# trinamic-controller.net
KiCad netlist of a schematic drawn in Altium Designer
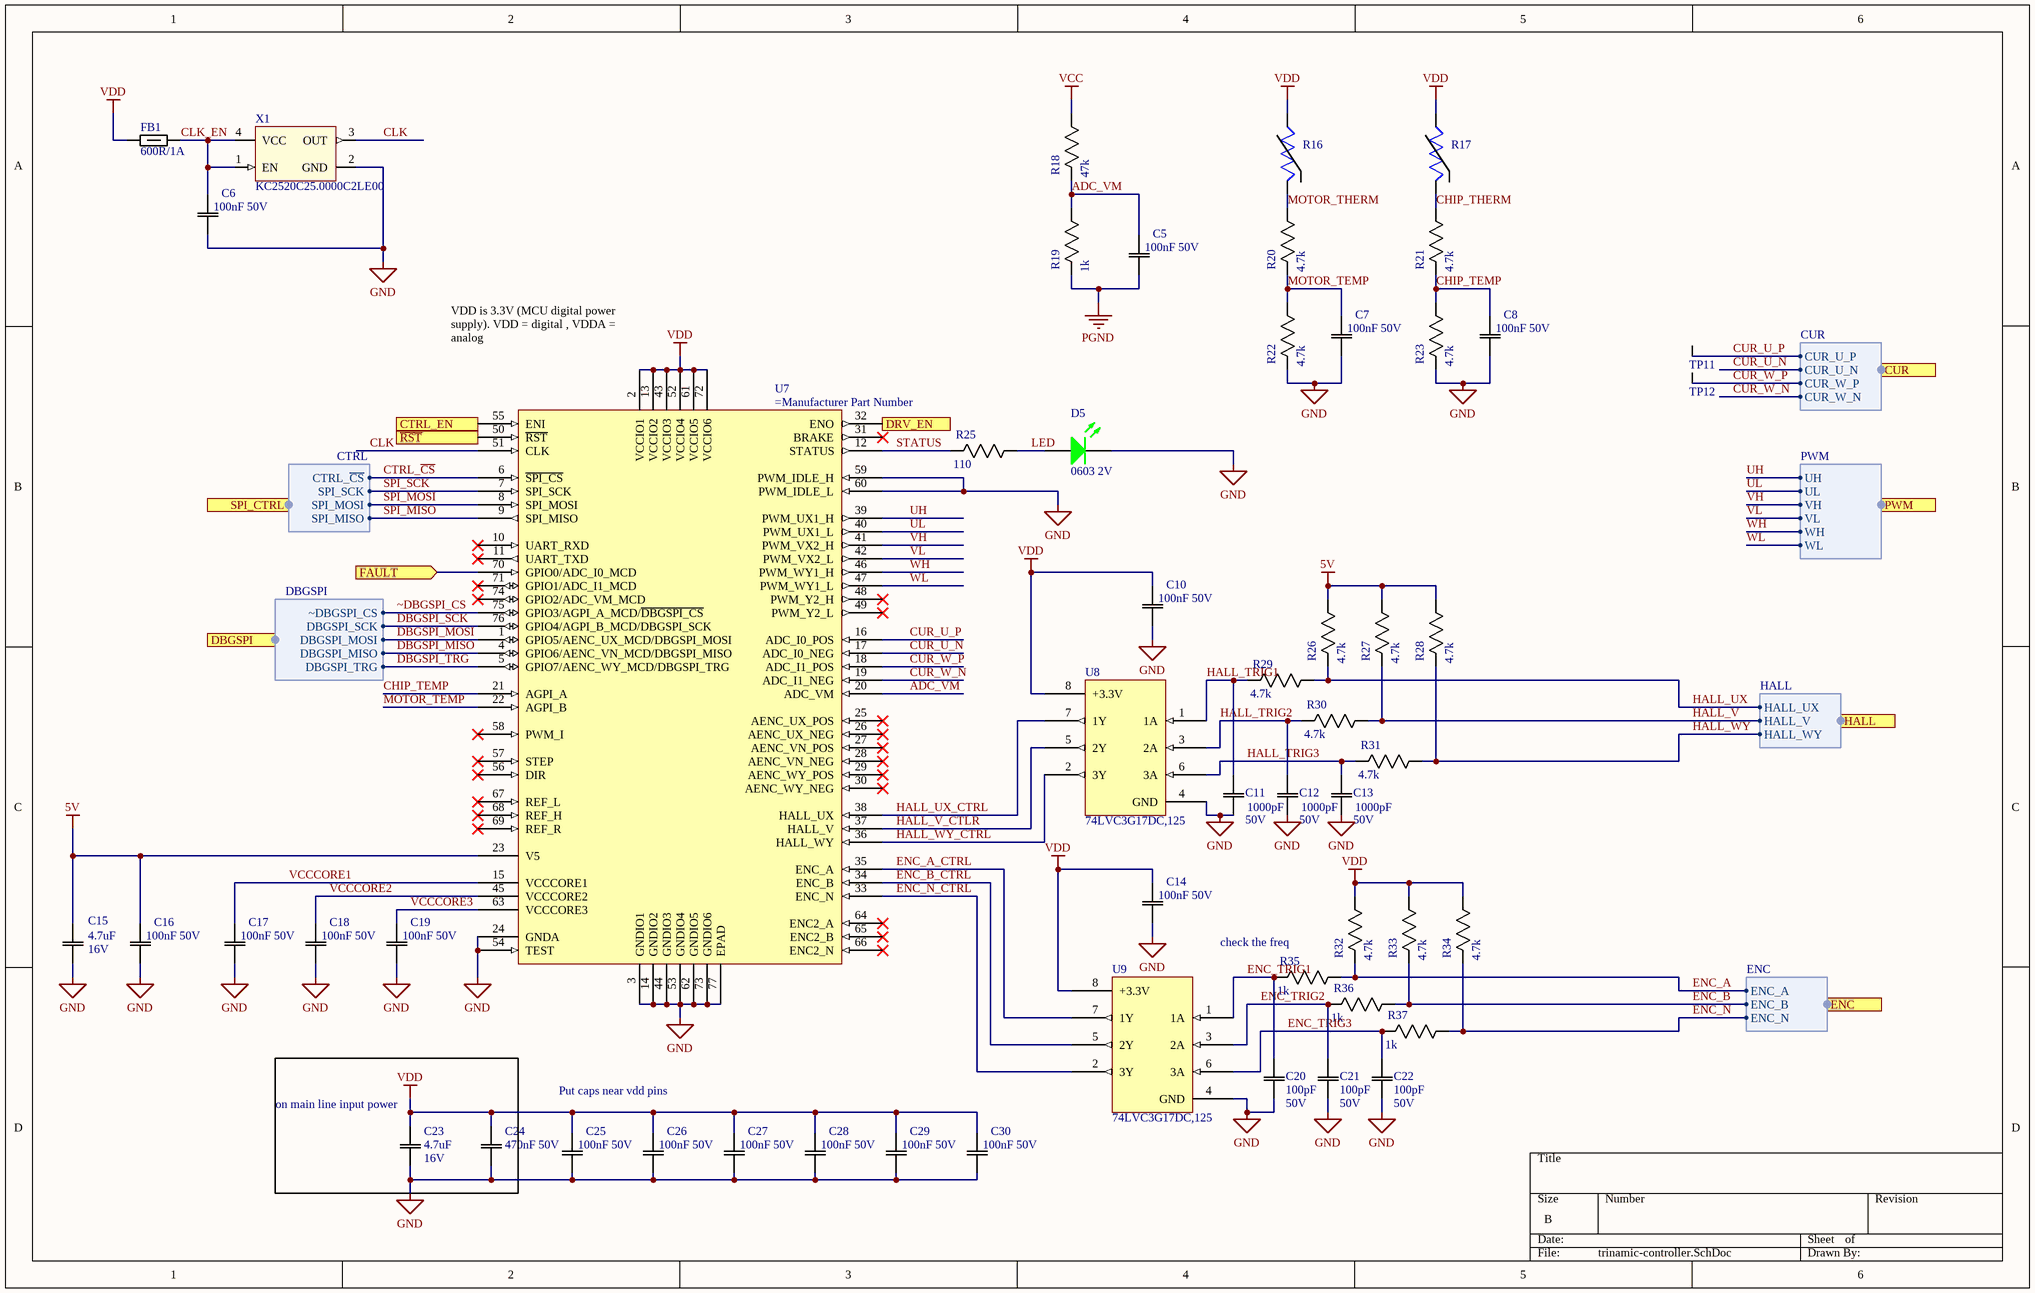
[diagram p0: trinamic-controller.SchDoc]

(export (version "E")
  (design (tool "Eeschema 10.0.6"))
  (components
    (comp (ref "C5")
      (value "100nF 50V")
      (footprint "0603")
      (description "Default Symbol for Capacitors")
      (fields (field (name "TOLERANCE") "10%") (field (name "PART NUMBER") "CAP 100nF 50V"))
      (libsource (lib "capacitor_library") (part "CAP_Default"))
    )
    (comp (ref "C6")
      (value "100nF 50V")
      (footprint "0603")
      (description "Default Symbol for Capacitors")
      (fields (field (name "TOLERANCE") "10%") (field (name "PART NUMBER") "CAP 100nF 50V"))
      (libsource (lib "capacitor_library") (part "CAP_Default"))
    )
    (comp (ref "C7")
      (value "100nF 50V")
      (footprint "0603")
      (description "Default Symbol for Capacitors")
      (fields (field (name "TOLERANCE") "10%") (field (name "PART NUMBER") "CAP 100nF 50V"))
      (libsource (lib "capacitor_library") (part "CAP_Default"))
    )
    (comp (ref "C8")
      (value "100nF 50V")
      (footprint "0603")
      (description "Default Symbol for Capacitors")
      (fields (field (name "TOLERANCE") "10%") (field (name "PART NUMBER") "CAP 100nF 50V"))
      (libsource (lib "capacitor_library") (part "CAP_Default"))
    )
    (comp (ref "C10")
      (value "100nF 50V")
      (footprint "0603")
      (description "Default Symbol for Capacitors")
      (fields (field (name "TOLERANCE") "10%") (field (name "PART NUMBER") "CAP 100nF 50V"))
      (libsource (lib "capacitor_library") (part "CAP_Default"))
    )
    (comp (ref "C11")
      (value "1000pF")
      (footprint "0603")
      (description "Default Symbol for Capacitors")
      (fields
        (field (name "TOLERANCE") "10%")
        (field (name "RATING") "50V")
        (field (name "PART NUMBER") "CAP 1000pF 50V")
      )
      (libsource (lib "capacitor_library") (part "CAP_Default"))
    )
    (comp (ref "C12")
      (value "1000pF")
      (footprint "0603")
      (description "Default Symbol for Capacitors")
      (fields
        (field (name "TOLERANCE") "10%")
        (field (name "RATING") "50V")
        (field (name "PART NUMBER") "CAP 1000pF 50V")
      )
      (libsource (lib "capacitor_library") (part "CAP_Default"))
    )
    (comp (ref "C13")
      (value "1000pF")
      (footprint "0603")
      (description "Default Symbol for Capacitors")
      (fields
        (field (name "TOLERANCE") "10%")
        (field (name "RATING") "50V")
        (field (name "PART NUMBER") "CAP 1000pF 50V")
      )
      (libsource (lib "capacitor_library") (part "CAP_Default"))
    )
    (comp (ref "C14")
      (value "100nF 50V")
      (footprint "0603")
      (description "Default Symbol for Capacitors")
      (fields (field (name "TOLERANCE") "10%") (field (name "PART NUMBER") "CAP 100nF 50V"))
      (libsource (lib "capacitor_library") (part "CAP_Default"))
    )
    (comp (ref "C15")
      (value "4.7uF")
      (footprint "0603")
      (description "Default Symbol for Capacitors")
      (fields
        (field (name "TOLERANCE") "10%")
        (field (name "RATING") "16V")
        (field (name "PART NUMBER") "CAP 4.7uF 16V")
      )
      (libsource (lib "capacitor_library") (part "CAP_Default"))
    )
    (comp (ref "C16")
      (value "100nF 50V")
      (footprint "0603")
      (description "Default Symbol for Capacitors")
      (fields (field (name "TOLERANCE") "10%") (field (name "PART NUMBER") "CAP 100nF 50V"))
      (libsource (lib "capacitor_library") (part "CAP_Default"))
    )
    (comp (ref "C17")
      (value "100nF 50V")
      (footprint "0603")
      (description "Default Symbol for Capacitors")
      (fields (field (name "TOLERANCE") "10%") (field (name "PART NUMBER") "CAP 100nF 50V"))
      (libsource (lib "capacitor_library") (part "CAP_Default"))
    )
    (comp (ref "C18")
      (value "100nF 50V")
      (footprint "0603")
      (description "Default Symbol for Capacitors")
      (fields (field (name "TOLERANCE") "10%") (field (name "PART NUMBER") "CAP 100nF 50V"))
      (libsource (lib "capacitor_library") (part "CAP_Default"))
    )
    (comp (ref "C19")
      (value "100nF 50V")
      (footprint "0603")
      (description "Default Symbol for Capacitors")
      (fields (field (name "TOLERANCE") "10%") (field (name "PART NUMBER") "CAP 100nF 50V"))
      (libsource (lib "capacitor_library") (part "CAP_Default"))
    )
    (comp (ref "C20")
      (value "100pF")
      (footprint "0603")
      (description "Default Symbol for Capacitors")
      (fields
        (field (name "TOLERANCE") "10%")
        (field (name "RATING") "50V")
        (field (name "PART NUMBER") "CAP 100pF 50V")
      )
      (libsource (lib "capacitor_library") (part "CAP_Default"))
    )
    (comp (ref "C21")
      (value "100pF")
      (footprint "0603")
      (description "Default Symbol for Capacitors")
      (fields
        (field (name "TOLERANCE") "10%")
        (field (name "RATING") "50V")
        (field (name "PART NUMBER") "CAP 100pF 50V")
      )
      (libsource (lib "capacitor_library") (part "CAP_Default"))
    )
    (comp (ref "C22")
      (value "100pF")
      (footprint "0603")
      (description "Default Symbol for Capacitors")
      (fields
        (field (name "TOLERANCE") "10%")
        (field (name "RATING") "50V")
        (field (name "PART NUMBER") "CAP 100pF 50V")
      )
      (libsource (lib "capacitor_library") (part "CAP_Default"))
    )
    (comp (ref "C23")
      (value "4.7uF")
      (footprint "0603")
      (description "Default Symbol for Capacitors")
      (fields
        (field (name "TOLERANCE") "10%")
        (field (name "RATING") "16V")
        (field (name "PART NUMBER") "CAP 4.7uF 16V")
      )
      (libsource (lib "capacitor_library") (part "CAP_Default"))
    )
    (comp (ref "C24")
      (value "470nF 50V")
      (footprint "0603")
      (description "Default Symbol for Capacitors")
      (fields (field (name "TOLERANCE") "10%") (field (name "PART NUMBER") "CAP 470nF 50V"))
      (libsource (lib "capacitor_library") (part "CAP_Default"))
    )
    (comp (ref "C25")
      (value "100nF 50V")
      (footprint "0603")
      (description "Default Symbol for Capacitors")
      (fields (field (name "TOLERANCE") "10%") (field (name "PART NUMBER") "CAP 100nF 50V"))
      (libsource (lib "capacitor_library") (part "CAP_Default"))
    )
    (comp (ref "C26")
      (value "100nF 50V")
      (footprint "0603")
      (description "Default Symbol for Capacitors")
      (fields (field (name "TOLERANCE") "10%") (field (name "PART NUMBER") "CAP 100nF 50V"))
      (libsource (lib "capacitor_library") (part "CAP_Default"))
    )
    (comp (ref "C27")
      (value "100nF 50V")
      (footprint "0603")
      (description "Default Symbol for Capacitors")
      (fields (field (name "TOLERANCE") "10%") (field (name "PART NUMBER") "CAP 100nF 50V"))
      (libsource (lib "capacitor_library") (part "CAP_Default"))
    )
    (comp (ref "C28")
      (value "100nF 50V")
      (footprint "0603")
      (description "Default Symbol for Capacitors")
      (fields (field (name "TOLERANCE") "10%") (field (name "PART NUMBER") "CAP 100nF 50V"))
      (libsource (lib "capacitor_library") (part "CAP_Default"))
    )
    (comp (ref "C29")
      (value "100nF 50V")
      (footprint "0603")
      (description "Default Symbol for Capacitors")
      (fields (field (name "TOLERANCE") "10%") (field (name "PART NUMBER") "CAP 100nF 50V"))
      (libsource (lib "capacitor_library") (part "CAP_Default"))
    )
    (comp (ref "C30")
      (value "100nF 50V")
      (footprint "0603")
      (description "Default Symbol for Capacitors")
      (fields (field (name "TOLERANCE") "10%") (field (name "PART NUMBER") "CAP 100nF 50V"))
      (libsource (lib "capacitor_library") (part "CAP_Default"))
    )
    (comp (ref "D5")
      (value "0603 2V")
      (footprint "0603 - LED")
      (description "LED Uni-Color Green 574nm 2-Pin Chip LED T/R")
      (fields (field (name "PART NUMBER") "LED GREEN SMD 0603"))
      (libsource (lib "Diode_Library") (part "LED GREEN SMD 0603"))
    )
    (comp (ref "FB1")
      (value "600R/1A")
      (footprint "0603")
      (fields (field (name "PART NUMBER") "FERRITE BEAD 200 MOHM 0603 1LN"))
      (libsource (lib "Inductor_Library") (part "FERRITE BEAD 200 MOHM 0603 1LN"))
    )
    (comp (ref "R16")
      (value "RES NTC 10k")
      (footprint "THERMISTOR TH")
      (fields (field (name "PART NUMBER") "RES NTC 10k TH") (field (name "TOLERANCE") "1%"))
      (libsource (lib "Resistor_Library") (part "RES NTC 10k"))
    )
    (comp (ref "R17")
      (value "RES NTC 10k")
      (footprint "0603")
      (fields (field (name "PART NUMBER") "RES NTC 10k CHIP") (field (name "TOLERANCE") "1%"))
      (libsource (lib "Resistor_Library") (part "RES NTC 10k"))
    )
    (comp (ref "R18")
      (value "47k")
      (footprint "0603")
      (description "Default Resistor Symbol")
      (fields (field (name "TOLERANCE") "1%") (field (name "PART NUMBER") "RES 47k 1/8W - 1%"))
      (libsource (lib "") (part "RES_DEFAULT_1"))
    )
    (comp (ref "R19")
      (value "1k")
      (footprint "0603")
      (description "Default Resistor Symbol")
      (fields (field (name "TOLERANCE") "1%") (field (name "PART NUMBER") "RES 1k 1/8W - 1%"))
      (libsource (lib "Resistor_Library") (part "RES_DEFAULT"))
    )
    (comp (ref "R20")
      (value "4.7k")
      (footprint "0603")
      (description "Default Resistor Symbol")
      (fields (field (name "TOLERANCE") "1%") (field (name "PART NUMBER") "RES 4.7k 1/8W - 1%"))
      (libsource (lib "") (part "RES_DEFAULT_1"))
    )
    (comp (ref "R21")
      (value "4.7k")
      (footprint "0603")
      (description "Default Resistor Symbol")
      (fields (field (name "TOLERANCE") "1%") (field (name "PART NUMBER") "RES 4.7k 1/8W - 1%"))
      (libsource (lib "") (part "RES_DEFAULT_1"))
    )
    (comp (ref "R22")
      (value "4.7k")
      (footprint "0603")
      (description "Default Resistor Symbol")
      (fields (field (name "TOLERANCE") "1%") (field (name "PART NUMBER") "RES 4.7k 1/8W - 1%"))
      (libsource (lib "") (part "RES_DEFAULT_1"))
    )
    (comp (ref "R23")
      (value "4.7k")
      (footprint "0603")
      (description "Default Resistor Symbol")
      (fields (field (name "TOLERANCE") "1%") (field (name "PART NUMBER") "RES 4.7k 1/8W - 1%"))
      (libsource (lib "") (part "RES_DEFAULT_1"))
    )
    (comp (ref "R25")
      (value "110")
      (footprint "0603")
      (description "Default Resistor Symbol")
      (fields (field (name "TOLERANCE") "1%") (field (name "PART NUMBER") "RES 110.0 1/8W - 1%"))
      (libsource (lib "Resistor_Library") (part "RES_DEFAULT"))
    )
    (comp (ref "R26")
      (value "4.7k")
      (footprint "0603")
      (description "Default Resistor Symbol")
      (fields (field (name "TOLERANCE") "5%") (field (name "PART NUMBER") "RES 4.7k 1/8W - 5%"))
      (libsource (lib "Resistor_Library") (part "RES_DEFAULT"))
    )
    (comp (ref "R27")
      (value "4.7k")
      (footprint "0603")
      (description "Default Resistor Symbol")
      (fields (field (name "TOLERANCE") "5%") (field (name "PART NUMBER") "RES 4.7k 1/8W - 5%"))
      (libsource (lib "Resistor_Library") (part "RES_DEFAULT"))
    )
    (comp (ref "R28")
      (value "4.7k")
      (footprint "0603")
      (description "Default Resistor Symbol")
      (fields (field (name "TOLERANCE") "5%") (field (name "PART NUMBER") "RES 4.7k 1/8W - 5%"))
      (libsource (lib "") (part "RES_DEFAULT_1"))
    )
    (comp (ref "R29")
      (value "4.7k")
      (footprint "0603")
      (description "Default Resistor Symbol")
      (fields (field (name "TOLERANCE") "5%") (field (name "PART NUMBER") "RES 4.7k 1/8W - 5%"))
      (libsource (lib "Resistor_Library") (part "RES_DEFAULT"))
    )
    (comp (ref "R30")
      (value "4.7k")
      (footprint "0603")
      (description "Default Resistor Symbol")
      (fields (field (name "TOLERANCE") "5%") (field (name "PART NUMBER") "RES 4.7k 1/8W - 5%"))
      (libsource (lib "Resistor_Library") (part "RES_DEFAULT"))
    )
    (comp (ref "R31")
      (value "4.7k")
      (footprint "0603")
      (description "Default Resistor Symbol")
      (fields (field (name "TOLERANCE") "5%") (field (name "PART NUMBER") "RES 4.7k 1/8W - 5%"))
      (libsource (lib "Resistor_Library") (part "RES_DEFAULT"))
    )
    (comp (ref "R32")
      (value "4.7k")
      (footprint "0603")
      (description "Default Resistor Symbol")
      (fields (field (name "TOLERANCE") "5%") (field (name "PART NUMBER") "RES 4.7k 1/8W - 5%"))
      (libsource (lib "Resistor_Library") (part "RES_DEFAULT"))
    )
    (comp (ref "R33")
      (value "4.7k")
      (footprint "0603")
      (description "Default Resistor Symbol")
      (fields (field (name "TOLERANCE") "5%") (field (name "PART NUMBER") "RES 4.7k 1/8W - 5%"))
      (libsource (lib "Resistor_Library") (part "RES_DEFAULT"))
    )
    (comp (ref "R34")
      (value "4.7k")
      (footprint "0603")
      (description "Default Resistor Symbol")
      (fields (field (name "TOLERANCE") "5%") (field (name "PART NUMBER") "RES 4.7k 1/8W - 5%"))
      (libsource (lib "") (part "RES_DEFAULT_1"))
    )
    (comp (ref "R35")
      (value "1k")
      (footprint "0603")
      (description "Default Resistor Symbol")
      (fields (field (name "TOLERANCE") "1%") (field (name "PART NUMBER") "RES 1k 1/8W - 1%"))
      (libsource (lib "") (part "RES_DEFAULT_1"))
    )
    (comp (ref "R36")
      (value "1k")
      (footprint "0603")
      (description "Default Resistor Symbol")
      (fields (field (name "TOLERANCE") "1%") (field (name "PART NUMBER") "RES 1k 1/8W - 1%"))
      (libsource (lib "Resistor_Library") (part "RES_DEFAULT"))
    )
    (comp (ref "R37")
      (value "1k")
      (footprint "0603")
      (description "Default Resistor Symbol")
      (fields (field (name "TOLERANCE") "1%") (field (name "PART NUMBER") "RES 1k 1/8W - 1%"))
      (libsource (lib "") (part "RES_DEFAULT_1"))
    )
    (comp (ref "TP11")
      (value "Test Point (Via)")
      (footprint "TP")
      (libsource (lib "IC_Library") (part "Test Point (Via)"))
    )
    (comp (ref "TP12")
      (value "Test Point (Via)")
      (footprint "TP")
      (libsource (lib "IC_Library") (part "Test Point (Via)"))
    )
    (comp (ref "U7")
      (value "~")
      (footprint "QFN40P1050X650X90_HS-77N")
      (description "Motor Driver, -40 To 125Deg C Rohs Compliant: Yes")
      (fields (field (name "PART NUMBER") "TMC4671"))
      (libsource (lib "IC_Library") (part "TMC4671"))
    )
    (comp (ref "U8")
      (value "74LVC3G17DC,125")
      (footprint "8-VSSOP")
      (description "IC BUFFER TRIPLE SCHMITT TRIGGER 5.5V VSSOP-8")
      (fields (field (name "PART NUMBER") "IC 74LVC3G17DC,125"))
      (libsource (lib "IC_Library") (part "IC 74LVC3G17DC,125"))
    )
    (comp (ref "U9")
      (value "74LVC3G17DC,125")
      (footprint "8-VSSOP")
      (description "IC BUFFER TRIPLE SCHMITT TRIGGER 5.5V VSSOP-8")
      (fields (field (name "PART NUMBER") "IC 74LVC3G17DC,125"))
      (libsource (lib "IC_Library") (part "IC 74LVC3G17DC,125"))
    )
    (comp (ref "X1")
      (value "KC2520C25.0000C2LE00")
      (footprint "KC2520C25.0000C2LE00")
      (description "Oscillator XO 25MHz ±15ppm 15pF CMOS 55% 2.5V/3.3V 4-Pin Mini-CSMD T/R")
      (fields (field (name "PART NUMBER") "XTAL OSC 25MHz 3.3V"))
      (libsource (lib "Oscillator_Library") (part "XTAL OSC 25MHz 3.3V"))
    )
  )
  (nets
    (net (code "7") (name "/ADC_VM") (class "Default")
      (node (ref "C5") (pin "2") (pinfunction "C2_2") (pintype "passive"))
      (node (ref "R18") (pin "2") (pinfunction "R2_2") (pintype "passive"))
      (node (ref "R19") (pin "1") (pinfunction "R1_1") (pintype "passive"))
      (node (ref "U7") (pin "20") (pinfunction "ADC_VM_20") (pintype "input"))
    )
    (net (code "8") (name "/CHIP_TEMP") (class "Default")
      (node (ref "C8") (pin "2") (pinfunction "C2_2") (pintype "passive"))
      (node (ref "R21") (pin "2") (pinfunction "R2_2") (pintype "passive"))
      (node (ref "R23") (pin "1") (pinfunction "R1_1") (pintype "passive"))
      (node (ref "U7") (pin "21") (pinfunction "AGPI_A_21") (pintype "input"))
    )
    (net (code "9") (name "/CHIP_THERM") (class "Default")
      (node (ref "R17") (pin "1") (pinfunction "1_1") (pintype "passive"))
      (node (ref "R21") (pin "1") (pinfunction "R1_1") (pintype "passive"))
    )
    (net (code "10") (name "/CLK") (class "Default")
      (node (ref "U7") (pin "51") (pinfunction "CLK_51") (pintype "input"))
      (node (ref "X1") (pin "3") (pinfunction "OUT_3") (pintype "output"))
    )
    (net (code "11") (name "/CLK_EN") (class "Default")
      (node (ref "C6") (pin "2") (pinfunction "C2_2") (pintype "passive"))
      (node (ref "FB1") (pin "2") (pinfunction "2_2") (pintype "passive"))
      (node (ref "X1") (pin "1") (pinfunction "EN_1") (pintype "input"))
      (node (ref "X1") (pin "4") (pinfunction "VCC_4") (pintype "power_in"))
    )
    (net (code "12") (name "/CTRL_EN") (class "Default")
      (node (ref "U7") (pin "55") (pinfunction "ENI_55") (pintype "input"))
    )
    (net (code "13") (name "/CTRL_~{CS}") (class "Default")
      (node (ref "U7") (pin "6") (pinfunction "~{SPI_CS}_6") (pintype "input"))
    )
    (net (code "14") (name "/CUR_U_N") (class "Default")
      (node (ref "U7") (pin "17") (pinfunction "ADC_I0_NEG_17") (pintype "input"))
    )
    (net (code "15") (name "/CUR_U_P") (class "Default")
      (node (ref "TP11") (pin "1") (pinfunction "1_1") (pintype "passive"))
      (node (ref "U7") (pin "16") (pinfunction "ADC_I0_POS_16") (pintype "input"))
    )
    (net (code "16") (name "/CUR_W_N") (class "Default")
      (node (ref "U7") (pin "19") (pinfunction "ADC_I1_NEG_19") (pintype "input"))
    )
    (net (code "17") (name "/CUR_W_P") (class "Default")
      (node (ref "TP12") (pin "1") (pinfunction "1_1") (pintype "passive"))
      (node (ref "U7") (pin "18") (pinfunction "ADC_I1_POS_18") (pintype "input"))
    )
    (net (code "18") (name "/DBGSPI_MISO") (class "Default")
      (node (ref "U7") (pin "4") (pinfunction "GPIO6/AENC_VN_MCD/DBGSPI_MISO_4") (pintype "bidirectional"))
    )
    (net (code "19") (name "/DBGSPI_MOSI") (class "Default")
      (node (ref "U7") (pin "1") (pinfunction "GPIO5/AENC_UX_MCD/DBGSPI_MOSI_1") (pintype "bidirectional"))
    )
    (net (code "20") (name "/DBGSPI_SCK") (class "Default")
      (node (ref "U7") (pin "76") (pinfunction "GPIO4/AGPI_B_MCD/DBGSPI_SCK_76") (pintype "bidirectional"))
    )
    (net (code "21") (name "/DBGSPI_TRG") (class "Default")
      (node (ref "U7") (pin "5") (pinfunction "GPIO7/AENC_WY_MCD/DBGSPI_TRG_5") (pintype "bidirectional"))
    )
    (net (code "22") (name "/DRV_EN") (class "Default")
      (node (ref "U7") (pin "32") (pinfunction "ENO_32") (pintype "output"))
    )
    (net (code "23") (name "/ENC_A") (class "Default")
      (node (ref "R32") (pin "2") (pinfunction "R2_2") (pintype "passive"))
      (node (ref "R35") (pin "1") (pinfunction "R1_1") (pintype "passive"))
    )
    (net (code "24") (name "/ENC_A_CTRL") (class "Default")
      (node (ref "U7") (pin "35") (pinfunction "ENC_A_35") (pintype "input"))
      (node (ref "U9") (pin "7") (pinfunction "1Y_7") (pintype "output"))
    )
    (net (code "25") (name "/ENC_B") (class "Default")
      (node (ref "R33") (pin "2") (pinfunction "R2_2") (pintype "passive"))
      (node (ref "R36") (pin "1") (pinfunction "R1_1") (pintype "passive"))
    )
    (net (code "26") (name "/ENC_B_CTRL") (class "Default")
      (node (ref "U7") (pin "34") (pinfunction "ENC_B_34") (pintype "input"))
      (node (ref "U9") (pin "5") (pinfunction "2Y_5") (pintype "output"))
    )
    (net (code "27") (name "/ENC_N") (class "Default")
      (node (ref "R34") (pin "2") (pinfunction "R2_2") (pintype "passive"))
      (node (ref "R37") (pin "1") (pinfunction "R1_1") (pintype "passive"))
    )
    (net (code "28") (name "/ENC_N_CTRL") (class "Default")
      (node (ref "U7") (pin "33") (pinfunction "ENC_N_33") (pintype "input"))
      (node (ref "U9") (pin "2") (pinfunction "3Y_2") (pintype "output"))
    )
    (net (code "29") (name "/ENC_TRIG1") (class "Default")
      (node (ref "C20") (pin "2") (pinfunction "C2_2") (pintype "passive"))
      (node (ref "R35") (pin "2") (pinfunction "R2_2") (pintype "passive"))
      (node (ref "U9") (pin "1") (pinfunction "1A_1") (pintype "input"))
    )
    (net (code "30") (name "/ENC_TRIG2") (class "Default")
      (node (ref "C21") (pin "2") (pinfunction "C2_2") (pintype "passive"))
      (node (ref "R36") (pin "2") (pinfunction "R2_2") (pintype "passive"))
      (node (ref "U9") (pin "3") (pinfunction "2A_3") (pintype "input"))
    )
    (net (code "31") (name "/ENC_TRIG3") (class "Default")
      (node (ref "C22") (pin "2") (pinfunction "C2_2") (pintype "passive"))
      (node (ref "R37") (pin "2") (pinfunction "R2_2") (pintype "passive"))
      (node (ref "U9") (pin "6") (pinfunction "3A_6") (pintype "input"))
    )
    (net (code "32") (name "/FAULT") (class "Default")
      (node (ref "U7") (pin "70") (pinfunction "GPIO0/ADC_I0_MCD_70") (pintype "input"))
    )
    (net (code "33") (name "/HALL_TRIG1") (class "Default")
      (node (ref "C11") (pin "2") (pinfunction "C2_2") (pintype "passive"))
      (node (ref "R29") (pin "2") (pinfunction "R2_2") (pintype "passive"))
      (node (ref "U8") (pin "1") (pinfunction "1A_1") (pintype "input"))
    )
    (net (code "34") (name "/HALL_TRIG2") (class "Default")
      (node (ref "C12") (pin "2") (pinfunction "C2_2") (pintype "passive"))
      (node (ref "R30") (pin "2") (pinfunction "R2_2") (pintype "passive"))
      (node (ref "U8") (pin "3") (pinfunction "2A_3") (pintype "input"))
    )
    (net (code "35") (name "/HALL_TRIG3") (class "Default")
      (node (ref "C13") (pin "2") (pinfunction "C2_2") (pintype "passive"))
      (node (ref "R31") (pin "2") (pinfunction "R2_2") (pintype "passive"))
      (node (ref "U8") (pin "6") (pinfunction "3A_6") (pintype "input"))
    )
    (net (code "36") (name "/HALL_UX") (class "Default")
      (node (ref "R26") (pin "2") (pinfunction "R2_2") (pintype "passive"))
      (node (ref "R29") (pin "1") (pinfunction "R1_1") (pintype "passive"))
    )
    (net (code "37") (name "/HALL_UX_CTRL") (class "Default")
      (node (ref "U7") (pin "38") (pinfunction "HALL_UX_38") (pintype "input"))
      (node (ref "U8") (pin "7") (pinfunction "1Y_7") (pintype "output"))
    )
    (net (code "38") (name "/HALL_V") (class "Default")
      (node (ref "R27") (pin "2") (pinfunction "R2_2") (pintype "passive"))
      (node (ref "R30") (pin "1") (pinfunction "R1_1") (pintype "passive"))
    )
    (net (code "39") (name "/HALL_V_CTLR") (class "Default")
      (node (ref "U7") (pin "37") (pinfunction "HALL_V_37") (pintype "input"))
      (node (ref "U8") (pin "5") (pinfunction "2Y_5") (pintype "output"))
    )
    (net (code "40") (name "/HALL_WY") (class "Default")
      (node (ref "R28") (pin "2") (pinfunction "R2_2") (pintype "passive"))
      (node (ref "R31") (pin "1") (pinfunction "R1_1") (pintype "passive"))
    )
    (net (code "41") (name "/HALL_WY_CTRL") (class "Default")
      (node (ref "U7") (pin "36") (pinfunction "HALL_WY_36") (pintype "input"))
      (node (ref "U8") (pin "2") (pinfunction "3Y_2") (pintype "output"))
    )
    (net (code "42") (name "/LED") (class "Default")
      (node (ref "D5") (pin "1") (pinfunction "A_1") (pintype "passive"))
      (node (ref "R25") (pin "1") (pinfunction "R1_1") (pintype "passive"))
    )
    (net (code "43") (name "/MOTOR_TEMP") (class "Default")
      (node (ref "C7") (pin "2") (pinfunction "C2_2") (pintype "passive"))
      (node (ref "R20") (pin "2") (pinfunction "R2_2") (pintype "passive"))
      (node (ref "R22") (pin "1") (pinfunction "R1_1") (pintype "passive"))
      (node (ref "U7") (pin "22") (pinfunction "AGPI_B_22") (pintype "input"))
    )
    (net (code "44") (name "/MOTOR_THERM") (class "Default")
      (node (ref "R16") (pin "1") (pinfunction "1_1") (pintype "passive"))
      (node (ref "R20") (pin "1") (pinfunction "R1_1") (pintype "passive"))
    )
    (net (code "45") (name "/SPI_MISO") (class "Default")
      (node (ref "U7") (pin "9") (pinfunction "SPI_MISO_9") (pintype "output"))
    )
    (net (code "46") (name "/SPI_MOSI") (class "Default")
      (node (ref "U7") (pin "8") (pinfunction "SPI_MOSI_8") (pintype "input"))
    )
    (net (code "47") (name "/SPI_SCK") (class "Default")
      (node (ref "U7") (pin "7") (pinfunction "SPI_SCK_7") (pintype "input"))
    )
    (net (code "48") (name "/STATUS") (class "Default")
      (node (ref "R25") (pin "2") (pinfunction "R2_2") (pintype "passive"))
      (node (ref "U7") (pin "12") (pinfunction "STATUS_12") (pintype "output"))
    )
    (net (code "49") (name "/UH") (class "Default")
      (node (ref "U7") (pin "39") (pinfunction "PWM_UX1_H_39") (pintype "output"))
    )
    (net (code "50") (name "/UL") (class "Default")
      (node (ref "U7") (pin "40") (pinfunction "PWM_UX1_L_40") (pintype "output"))
    )
    (net (code "51") (name "/VCCCORE1") (class "Default")
      (node (ref "C17") (pin "2") (pinfunction "C2_2") (pintype "passive"))
      (node (ref "U7") (pin "15") (pinfunction "VCCCORE1_15") (pintype "power_in"))
    )
    (net (code "52") (name "/VCCCORE2") (class "Default")
      (node (ref "C18") (pin "2") (pinfunction "C2_2") (pintype "passive"))
      (node (ref "U7") (pin "45") (pinfunction "VCCCORE2_45") (pintype "power_in"))
    )
    (net (code "53") (name "/VCCCORE3") (class "Default")
      (node (ref "C19") (pin "2") (pinfunction "C2_2") (pintype "passive"))
      (node (ref "U7") (pin "63") (pinfunction "VCCCORE3_63") (pintype "power_in"))
    )
    (net (code "54") (name "/VH") (class "Default")
      (node (ref "U7") (pin "41") (pinfunction "PWM_VX2_H_41") (pintype "output"))
    )
    (net (code "55") (name "/VL") (class "Default")
      (node (ref "U7") (pin "42") (pinfunction "PWM_VX2_L_42") (pintype "output"))
    )
    (net (code "56") (name "/WH") (class "Default")
      (node (ref "U7") (pin "46") (pinfunction "PWM_WY1_H_46") (pintype "output"))
    )
    (net (code "57") (name "/WL") (class "Default")
      (node (ref "U7") (pin "47") (pinfunction "PWM_WY1_L_47") (pintype "output"))
    )
    (net (code "64") (name "/~DBGSPI_CS") (class "Default")
      (node (ref "U7") (pin "75") (pinfunction "GPIO3/AGPI_A_MCD/~{DBGSPI_CS}_75") (pintype "bidirectional"))
    )
    (net (code "65") (name "/~{RST}") (class "Default")
      (node (ref "U7") (pin "50") (pinfunction "~{RST}_50") (pintype "input"))
    )
    (net (code "66") (name "5V") (class "Default")
      (node (ref "C15") (pin "2") (pinfunction "C2_2") (pintype "passive"))
      (node (ref "C16") (pin "2") (pinfunction "C2_2") (pintype "passive"))
      (node (ref "R26") (pin "1") (pinfunction "R1_1") (pintype "passive"))
      (node (ref "R27") (pin "1") (pinfunction "R1_1") (pintype "passive"))
      (node (ref "R28") (pin "1") (pinfunction "R1_1") (pintype "passive"))
      (node (ref "U7") (pin "23") (pinfunction "V5_23") (pintype "power_in"))
    )
    (net (code "67") (name "GND") (class "Default")
      (node (ref "C10") (pin "1") (pinfunction "C1_1") (pintype "passive"))
      (node (ref "C11") (pin "1") (pinfunction "C1_1") (pintype "passive"))
      (node (ref "C12") (pin "1") (pinfunction "C1_1") (pintype "passive"))
      (node (ref "C13") (pin "1") (pinfunction "C1_1") (pintype "passive"))
      (node (ref "C14") (pin "1") (pinfunction "C1_1") (pintype "passive"))
      (node (ref "C15") (pin "1") (pinfunction "C1_1") (pintype "passive"))
      (node (ref "C16") (pin "1") (pinfunction "C1_1") (pintype "passive"))
      (node (ref "C17") (pin "1") (pinfunction "C1_1") (pintype "passive"))
      (node (ref "C18") (pin "1") (pinfunction "C1_1") (pintype "passive"))
      (node (ref "C19") (pin "1") (pinfunction "C1_1") (pintype "passive"))
      (node (ref "C20") (pin "1") (pinfunction "C1_1") (pintype "passive"))
      (node (ref "C21") (pin "1") (pinfunction "C1_1") (pintype "passive"))
      (node (ref "C22") (pin "1") (pinfunction "C1_1") (pintype "passive"))
      (node (ref "C23") (pin "1") (pinfunction "C1_1") (pintype "passive"))
      (node (ref "C24") (pin "1") (pinfunction "C1_1") (pintype "passive"))
      (node (ref "C25") (pin "1") (pinfunction "C1_1") (pintype "passive"))
      (node (ref "C26") (pin "1") (pinfunction "C1_1") (pintype "passive"))
      (node (ref "C27") (pin "1") (pinfunction "C1_1") (pintype "passive"))
      (node (ref "C28") (pin "1") (pinfunction "C1_1") (pintype "passive"))
      (node (ref "C29") (pin "1") (pinfunction "C1_1") (pintype "passive"))
      (node (ref "C30") (pin "1") (pinfunction "C1_1") (pintype "passive"))
      (node (ref "C6") (pin "1") (pinfunction "C1_1") (pintype "passive"))
      (node (ref "C7") (pin "1") (pinfunction "C1_1") (pintype "passive"))
      (node (ref "C8") (pin "1") (pinfunction "C1_1") (pintype "passive"))
      (node (ref "D5") (pin "2") (pinfunction "K_2") (pintype "passive"))
      (node (ref "R22") (pin "2") (pinfunction "R2_2") (pintype "passive"))
      (node (ref "R23") (pin "2") (pinfunction "R2_2") (pintype "passive"))
      (node (ref "U7") (pin "14") (pinfunction "GNDIO2_14") (pintype "power_in"))
      (node (ref "U7") (pin "24") (pinfunction "GNDA_24") (pintype "power_in"))
      (node (ref "U7") (pin "3") (pinfunction "GNDIO1_3") (pintype "power_in"))
      (node (ref "U7") (pin "44") (pinfunction "GNDIO3_44") (pintype "power_in"))
      (node (ref "U7") (pin "53") (pinfunction "GNDIO4_53") (pintype "power_in"))
      (node (ref "U7") (pin "54") (pinfunction "TEST_54") (pintype "input"))
      (node (ref "U7") (pin "59") (pinfunction "PWM_IDLE_H_59") (pintype "input"))
      (node (ref "U7") (pin "60") (pinfunction "PWM_IDLE_L_60") (pintype "input"))
      (node (ref "U7") (pin "62") (pinfunction "GNDIO5_62") (pintype "power_in"))
      (node (ref "U7") (pin "73") (pinfunction "GNDIO6_73") (pintype "power_in"))
      (node (ref "U7") (pin "77") (pinfunction "EPAD_77") (pintype "passive"))
      (node (ref "U8") (pin "4") (pinfunction "GND_4") (pintype "power_in"))
      (node (ref "U9") (pin "4") (pinfunction "GND_4") (pintype "power_in"))
      (node (ref "X1") (pin "2") (pinfunction "GND_2") (pintype "power_in"))
    )
    (net (code "68") (name "PGND") (class "Default")
      (node (ref "C5") (pin "1") (pinfunction "C1_1") (pintype "passive"))
      (node (ref "R19") (pin "2") (pinfunction "R2_2") (pintype "passive"))
    )
    (net (code "69") (name "VCC") (class "Default")
      (node (ref "R18") (pin "1") (pinfunction "R1_1") (pintype "passive"))
    )
    (net (code "70") (name "VDD") (class "Default")
      (node (ref "C10") (pin "2") (pinfunction "C2_2") (pintype "passive"))
      (node (ref "C14") (pin "2") (pinfunction "C2_2") (pintype "passive"))
      (node (ref "C23") (pin "2") (pinfunction "C2_2") (pintype "passive"))
      (node (ref "C24") (pin "2") (pinfunction "C2_2") (pintype "passive"))
      (node (ref "C25") (pin "2") (pinfunction "C2_2") (pintype "passive"))
      (node (ref "C26") (pin "2") (pinfunction "C2_2") (pintype "passive"))
      (node (ref "C27") (pin "2") (pinfunction "C2_2") (pintype "passive"))
      (node (ref "C28") (pin "2") (pinfunction "C2_2") (pintype "passive"))
      (node (ref "C29") (pin "2") (pinfunction "C2_2") (pintype "passive"))
      (node (ref "C30") (pin "2") (pinfunction "C2_2") (pintype "passive"))
      (node (ref "FB1") (pin "1") (pinfunction "1_1") (pintype "passive"))
      (node (ref "R16") (pin "2") (pinfunction "2_2") (pintype "passive"))
      (node (ref "R17") (pin "2") (pinfunction "2_2") (pintype "passive"))
      (node (ref "R32") (pin "1") (pinfunction "R1_1") (pintype "passive"))
      (node (ref "R33") (pin "1") (pinfunction "R1_1") (pintype "passive"))
      (node (ref "R34") (pin "1") (pinfunction "R1_1") (pintype "passive"))
      (node (ref "U7") (pin "13") (pinfunction "VCCIO2_13") (pintype "power_in"))
      (node (ref "U7") (pin "2") (pinfunction "VCCIO1_2") (pintype "power_in"))
      (node (ref "U7") (pin "43") (pinfunction "VCCIO3_43") (pintype "power_in"))
      (node (ref "U7") (pin "52") (pinfunction "VCCIO4_52") (pintype "power_in"))
      (node (ref "U7") (pin "61") (pinfunction "VCCIO5_61") (pintype "power_in"))
      (node (ref "U7") (pin "72") (pinfunction "VCCIO6_72") (pintype "power_in"))
      (node (ref "U8") (pin "8") (pinfunction "+3.3V_8") (pintype "power_in"))
      (node (ref "U9") (pin "8") (pinfunction "+3.3V_8") (pintype "power_in"))
    )
    (net (code "71") (name "unconnected-(U7-AENC_UX_NEG-Pad26)") (class "Default")
      (node (ref "U7") (pin "26") (pinfunction "AENC_UX_NEG_26") (pintype "input+no_connect"))
    )
    (net (code "72") (name "unconnected-(U7-AENC_UX_POS-Pad25)") (class "Default")
      (node (ref "U7") (pin "25") (pinfunction "AENC_UX_POS_25") (pintype "input+no_connect"))
    )
    (net (code "73") (name "unconnected-(U7-AENC_VN_NEG-Pad28)") (class "Default")
      (node (ref "U7") (pin "28") (pinfunction "AENC_VN_NEG_28") (pintype "input+no_connect"))
    )
    (net (code "74") (name "unconnected-(U7-AENC_VN_POS-Pad27)") (class "Default")
      (node (ref "U7") (pin "27") (pinfunction "AENC_VN_POS_27") (pintype "input+no_connect"))
    )
    (net (code "75") (name "unconnected-(U7-AENC_WY_NEG-Pad30)") (class "Default")
      (node (ref "U7") (pin "30") (pinfunction "AENC_WY_NEG_30") (pintype "input+no_connect"))
    )
    (net (code "76") (name "unconnected-(U7-AENC_WY_POS-Pad29)") (class "Default")
      (node (ref "U7") (pin "29") (pinfunction "AENC_WY_POS_29") (pintype "input+no_connect"))
    )
    (net (code "77") (name "unconnected-(U7-BRAKE-Pad31)") (class "Default")
      (node (ref "U7") (pin "31") (pinfunction "BRAKE_31") (pintype "output+no_connect"))
    )
    (net (code "78") (name "unconnected-(U7-DIR-Pad56)") (class "Default")
      (node (ref "U7") (pin "56") (pinfunction "DIR_56") (pintype "input+no_connect"))
    )
    (net (code "79") (name "unconnected-(U7-ENC2_A-Pad64)") (class "Default")
      (node (ref "U7") (pin "64") (pinfunction "ENC2_A_64") (pintype "input+no_connect"))
    )
    (net (code "80") (name "unconnected-(U7-ENC2_B-Pad65)") (class "Default")
      (node (ref "U7") (pin "65") (pinfunction "ENC2_B_65") (pintype "input+no_connect"))
    )
    (net (code "81") (name "unconnected-(U7-ENC2_N-Pad66)") (class "Default")
      (node (ref "U7") (pin "66") (pinfunction "ENC2_N_66") (pintype "input+no_connect"))
    )
    (net (code "82") (name "unconnected-(U7-GPIO1{slash}ADC_I1_MCD-Pad71)") (class "Default")
      (node (ref "U7") (pin "71") (pinfunction "GPIO1/ADC_I1_MCD_71") (pintype "bidirectional+no_connect"))
    )
    (net (code "83") (name "unconnected-(U7-GPIO2{slash}ADC_VM_MCD-Pad74)") (class "Default")
      (node (ref "U7") (pin "74") (pinfunction "GPIO2/ADC_VM_MCD_74") (pintype "bidirectional+no_connect"))
    )
    (net (code "84") (name "unconnected-(U7-PWM_I-Pad58)") (class "Default")
      (node (ref "U7") (pin "58") (pinfunction "PWM_I_58") (pintype "input+no_connect"))
    )
    (net (code "85") (name "unconnected-(U7-PWM_Y2_H-Pad48)") (class "Default")
      (node (ref "U7") (pin "48") (pinfunction "PWM_Y2_H_48") (pintype "output+no_connect"))
    )
    (net (code "86") (name "unconnected-(U7-PWM_Y2_L-Pad49)") (class "Default")
      (node (ref "U7") (pin "49") (pinfunction "PWM_Y2_L_49") (pintype "output+no_connect"))
    )
    (net (code "87") (name "unconnected-(U7-REF_H-Pad68)") (class "Default")
      (node (ref "U7") (pin "68") (pinfunction "REF_H_68") (pintype "input+no_connect"))
    )
    (net (code "88") (name "unconnected-(U7-REF_L-Pad67)") (class "Default")
      (node (ref "U7") (pin "67") (pinfunction "REF_L_67") (pintype "input+no_connect"))
    )
    (net (code "89") (name "unconnected-(U7-REF_R-Pad69)") (class "Default")
      (node (ref "U7") (pin "69") (pinfunction "REF_R_69") (pintype "input+no_connect"))
    )
    (net (code "90") (name "unconnected-(U7-STEP-Pad57)") (class "Default")
      (node (ref "U7") (pin "57") (pinfunction "STEP_57") (pintype "input+no_connect"))
    )
    (net (code "91") (name "unconnected-(U7-UART_RXD-Pad10)") (class "Default")
      (node (ref "U7") (pin "10") (pinfunction "UART_RXD_10") (pintype "input+no_connect"))
    )
    (net (code "92") (name "unconnected-(U7-UART_TXD-Pad11)") (class "Default")
      (node (ref "U7") (pin "11") (pinfunction "UART_TXD_11") (pintype "output+no_connect"))
    )
  )
)
